# Launch_Tower_Ignition_Board_v6-4.net
KiCad netlist of a schematic drawn in EAGLE
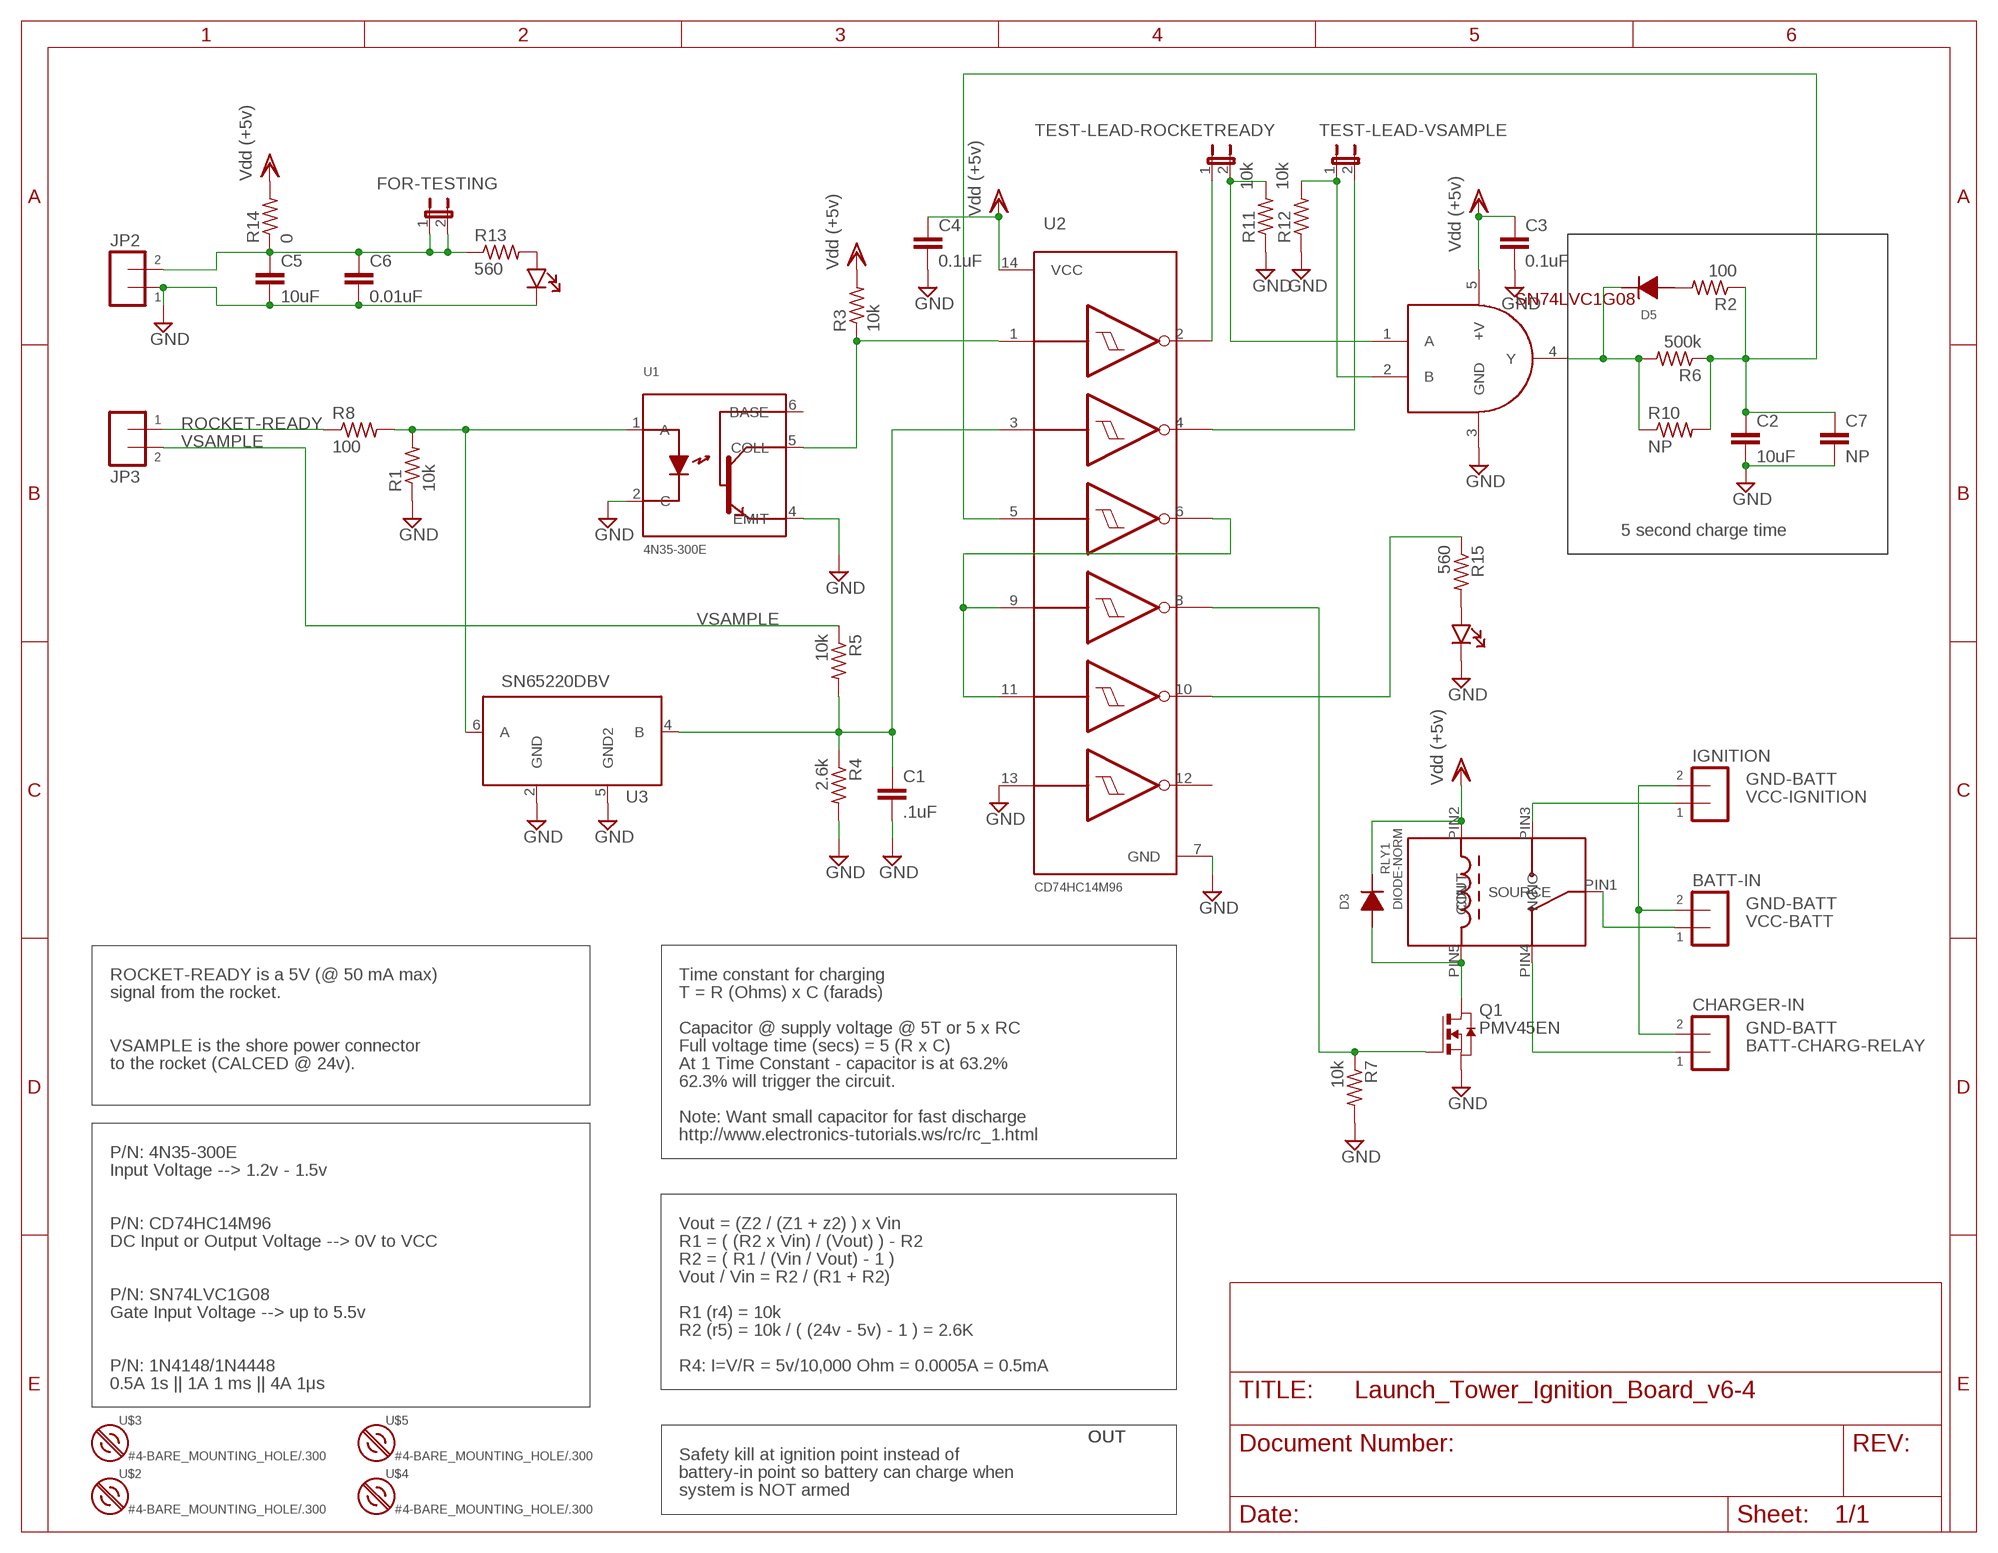
[diagram p0: schematic, sheet 1]

(export (version "E")
  (design (tool "Eeschema 10.0.6"))
  (components
    (comp (ref "BATT-IN")
      (value "SCREW-TERMINAL-5MM")
      (footprint "eagle-import:SCREW-TERM-5MM")
      (libsource (lib "eagle-import") (part "SCREW-TERMINAL-5MM"))
    )
    (comp (ref "C1")
      (value ".1uF")
      (footprint "eagle-import:0805-B")
      (libsource (lib "eagle-import") (part "C-EU0805-B"))
    )
    (comp (ref "C2")
      (value "10uF")
      (footprint "eagle-import:0805-B")
      (libsource (lib "eagle-import") (part "C-EU0805-B"))
    )
    (comp (ref "C3")
      (value "0.1uF")
      (footprint "eagle-import:0805-B")
      (libsource (lib "eagle-import") (part "C-EU0805-B"))
    )
    (comp (ref "C4")
      (value "0.1uF")
      (footprint "eagle-import:0805-B")
      (libsource (lib "eagle-import") (part "C-EU0805-B"))
    )
    (comp (ref "C5")
      (value "10uF")
      (footprint "eagle-import:0805-B")
      (libsource (lib "eagle-import") (part "C-EU0805-B"))
    )
    (comp (ref "C6")
      (value "0.01uF")
      (footprint "eagle-import:0805-B")
      (libsource (lib "eagle-import") (part "C-EU0805-B"))
    )
    (comp (ref "C7")
      (value "NP")
      (footprint "eagle-import:CAP-PTH-SMALL")
      (libsource (lib "eagle-import") (part "CAPPTH"))
    )
    (comp (ref "CHARGER-IN")
      (value "SCREW-TERMINAL-5MM")
      (footprint "eagle-import:SCREW-TERM-5MM")
      (libsource (lib "eagle-import") (part "SCREW-TERMINAL-5MM"))
    )
    (comp (ref "D3")
      (value "DIODE-NORM")
      (footprint "eagle-import:DIODE")
      (libsource (lib "eagle-import") (part "DIODE-NORM"))
    )
    (comp (ref "D5")
      (value "DIODE-NORM")
      (footprint "eagle-import:DIODE")
      (libsource (lib "eagle-import") (part "DIODE-NORM"))
    )
    (comp (ref "FOR-TESTING")
      (value "JUMPER-2PTH")
      (footprint "eagle-import:1X02")
      (libsource (lib "eagle-import") (part "JUMPER-2PTH"))
    )
    (comp (ref "IGNITION")
      (value "SCREW-TERMINAL-5MM")
      (footprint "eagle-import:SCREW-TERM-5MM")
      (libsource (lib "eagle-import") (part "SCREW-TERMINAL-5MM"))
    )
    (comp (ref "JP2")
      (value "SCREW-TERMINAL-5MM")
      (footprint "eagle-import:SCREW-TERM-5MM")
      (libsource (lib "eagle-import") (part "SCREW-TERMINAL-5MM"))
    )
    (comp (ref "JP3")
      (value "SCREW-TERMINAL-5MM")
      (footprint "eagle-import:SCREW-TERM-5MM")
      (libsource (lib "eagle-import") (part "SCREW-TERMINAL-5MM"))
    )
    (comp (ref "LED-POWER-INDICATOR")
      (value "LED-550-XX04")
      (footprint "eagle-import:LED-550")
      (libsource (lib "eagle-import") (part "LED-550-XX04"))
    )
    (comp (ref "LED-POWER-INDICATOR1")
      (value "LED-550-XX04")
      (footprint "eagle-import:LED-550")
      (libsource (lib "eagle-import") (part "LED-550-XX04"))
    )
    (comp (ref "Q1")
      (value "PMV45EN")
      (footprint "eagle-import:SOT23")
      (libsource (lib "eagle-import") (part "PMV45EN"))
    )
    (comp (ref "R1")
      (value "10k")
      (footprint "eagle-import:0805-B")
      (libsource (lib "eagle-import") (part "R-US_0805-B"))
    )
    (comp (ref "R2")
      (value "100")
      (footprint "eagle-import:0805-B")
      (libsource (lib "eagle-import") (part "R-US_0805-B"))
    )
    (comp (ref "R3")
      (value "10k")
      (footprint "eagle-import:0805-B")
      (libsource (lib "eagle-import") (part "R-US_0805-B"))
    )
    (comp (ref "R4")
      (value "2.6k")
      (footprint "eagle-import:0805-B")
      (libsource (lib "eagle-import") (part "R-US_0805-B"))
    )
    (comp (ref "R5")
      (value "10k")
      (footprint "eagle-import:0805-B")
      (libsource (lib "eagle-import") (part "R-US_0805-B"))
    )
    (comp (ref "R6")
      (value "500k")
      (footprint "eagle-import:0805-B")
      (libsource (lib "eagle-import") (part "R-US_0805-B"))
    )
    (comp (ref "R7")
      (value "10k")
      (footprint "eagle-import:0805-B")
      (libsource (lib "eagle-import") (part "R-US_0805-B"))
    )
    (comp (ref "R8")
      (value "100")
      (footprint "eagle-import:0805-B")
      (libsource (lib "eagle-import") (part "R-US_0805-B"))
    )
    (comp (ref "R10")
      (value "NP")
      (footprint "eagle-import:0207_10")
      (libsource (lib "eagle-import") (part "R-US_0207/10"))
    )
    (comp (ref "R11")
      (value "10k")
      (footprint "eagle-import:0805-B")
      (libsource (lib "eagle-import") (part "R-US_0805-B"))
    )
    (comp (ref "R12")
      (value "10k")
      (footprint "eagle-import:0805-B")
      (libsource (lib "eagle-import") (part "R-US_0805-B"))
    )
    (comp (ref "R13")
      (value "560")
      (footprint "eagle-import:0805-B")
      (libsource (lib "eagle-import") (part "R-US_0805-B"))
    )
    (comp (ref "R14")
      (value "0")
      (footprint "eagle-import:0805-B")
      (libsource (lib "eagle-import") (part "R-US_0805-B"))
    )
    (comp (ref "R15")
      (value "560")
      (footprint "eagle-import:0805-B")
      (libsource (lib "eagle-import") (part "R-US_0805-B"))
    )
    (comp (ref "RLY1")
      (value "RELAY-2")
      (footprint "eagle-import:G5LA")
      (libsource (lib "eagle-import") (part "RELAY-2"))
    )
    (comp (ref "TEST-LEAD-ROCKETREADY")
      (value "JUMPER-2PTH")
      (footprint "eagle-import:1X02")
      (libsource (lib "eagle-import") (part "JUMPER-2PTH"))
    )
    (comp (ref "TEST-LEAD-VSAMPLE")
      (value "JUMPER-2PTH")
      (footprint "eagle-import:1X02")
      (libsource (lib "eagle-import") (part "JUMPER-2PTH"))
    )
    (comp (ref "U$2")
      (value "#4-BARE_MOUNTING_HOLE/.300")
      (footprint "eagle-import:#4_.300-BARE+STD_NUT_OR_STAR_WASHER")
      (libsource (lib "eagle-import") (part "#4-BARE_MOUNTING_HOLE/.300"))
    )
    (comp (ref "U$3")
      (value "#4-BARE_MOUNTING_HOLE/.300")
      (footprint "eagle-import:#4_.300-BARE+STD_NUT_OR_STAR_WASHER")
      (libsource (lib "eagle-import") (part "#4-BARE_MOUNTING_HOLE/.300"))
    )
    (comp (ref "U$4")
      (value "#4-BARE_MOUNTING_HOLE/.300")
      (footprint "eagle-import:#4_.300-BARE+STD_NUT_OR_STAR_WASHER")
      (libsource (lib "eagle-import") (part "#4-BARE_MOUNTING_HOLE/.300"))
    )
    (comp (ref "U$5")
      (value "#4-BARE_MOUNTING_HOLE/.300")
      (footprint "eagle-import:#4_.300-BARE+STD_NUT_OR_STAR_WASHER")
      (libsource (lib "eagle-import") (part "#4-BARE_MOUNTING_HOLE/.300"))
    )
    (comp (ref "U1")
      (value "OPTOISOLATOR")
      (footprint "eagle-import:4N35-300E")
      (libsource (lib "eagle-import") (part "OPTOISOLATOR"))
    )
    (comp (ref "U2")
      (value "INVERT GATES")
      (footprint "eagle-import:INVERTSOIC14")
      (libsource (lib "eagle-import") (part "HEX_INV_SHMITT_TRIG"))
    )
    (comp (ref "U3")
      (value "SN65220DBV")
      (footprint "eagle-import:SOT23-6L")
      (libsource (lib "eagle-import") (part "SN65220DBV"))
    )
    (comp (ref "U4")
      (value "AND GATE")
      (footprint "eagle-import:SOT23-5")
      (libsource (lib "eagle-import") (part "SN74LVC1G08"))
    )
  )
  (nets
    (net (code "1") (name "/BATT-CHARG-RELAY") (class "Default")
      (node (ref "CHARGER-IN") (pin "1") (pinfunction "1_1") (pintype "passive"))
      (node (ref "RLY1") (pin "PIN4") (pinfunction "NC_PIN4") (pintype "bidirectional"))
    )
    (net (code "2") (name "/GND-BATT") (class "Default")
      (node (ref "BATT-IN") (pin "2") (pinfunction "2_2") (pintype "passive"))
      (node (ref "CHARGER-IN") (pin "2") (pinfunction "2_2") (pintype "passive"))
      (node (ref "IGNITION") (pin "2") (pinfunction "2_2") (pintype "passive"))
    )
    (net (code "3") (name "/ROCKET-READY") (class "Default")
      (node (ref "R1") (pin "2") (pinfunction "2_2") (pintype "passive"))
      (node (ref "R8") (pin "2") (pinfunction "2_2") (pintype "passive"))
      (node (ref "U1") (pin "1") (pinfunction "A_1") (pintype "passive"))
      (node (ref "U3") (pin "6") (pinfunction "A_6") (pintype "passive"))
    )
    (net (code "4") (name "/VCC-BATT") (class "Default")
      (node (ref "BATT-IN") (pin "1") (pinfunction "1_1") (pintype "passive"))
      (node (ref "RLY1") (pin "PIN1") (pinfunction "SOURCE_PIN1") (pintype "bidirectional"))
    )
    (net (code "5") (name "/VCC-IGNITION") (class "Default")
      (node (ref "IGNITION") (pin "1") (pinfunction "1_1") (pintype "passive"))
      (node (ref "RLY1") (pin "PIN3") (pinfunction "NO_PIN3") (pintype "bidirectional"))
    )
    (net (code "6") (name "/VSAMPLE") (class "Default")
      (node (ref "JP3") (pin "2") (pinfunction "2_2") (pintype "passive"))
      (node (ref "R5") (pin "1") (pinfunction "1_1") (pintype "passive"))
    )
    (net (code "7") (name "GND") (class "Default")
      (node (ref "C1") (pin "2") (pinfunction "2_2") (pintype "passive"))
      (node (ref "C2") (pin "2") (pinfunction "2_2") (pintype "passive"))
      (node (ref "C3") (pin "2") (pinfunction "2_2") (pintype "passive"))
      (node (ref "C4") (pin "2") (pinfunction "2_2") (pintype "passive"))
      (node (ref "C5") (pin "2") (pinfunction "2_2") (pintype "passive"))
      (node (ref "C6") (pin "2") (pinfunction "2_2") (pintype "passive"))
      (node (ref "C7") (pin "2") (pinfunction "2_2") (pintype "passive"))
      (node (ref "JP2") (pin "1") (pinfunction "1_1") (pintype "passive"))
      (node (ref "LED-POWER-INDICATOR") (pin "CATHODE") (pinfunction "CATHODE_CATHODE") (pintype "bidirectional"))
      (node (ref "LED-POWER-INDICATOR1") (pin "CATHODE") (pinfunction "CATHODE_CATHODE") (pintype "bidirectional"))
      (node (ref "Q1") (pin "2") (pinfunction "S_2") (pintype "passive"))
      (node (ref "R1") (pin "1") (pinfunction "1_1") (pintype "passive"))
      (node (ref "R11") (pin "1") (pinfunction "1_1") (pintype "passive"))
      (node (ref "R12") (pin "1") (pinfunction "1_1") (pintype "passive"))
      (node (ref "R4") (pin "2") (pinfunction "2_2") (pintype "passive"))
      (node (ref "R7") (pin "2") (pinfunction "2_2") (pintype "passive"))
      (node (ref "U1") (pin "2") (pinfunction "C_2") (pintype "passive"))
      (node (ref "U1") (pin "4") (pinfunction "EMIT_4") (pintype "passive"))
      (node (ref "U2") (pin "13") (pinfunction "6A_13") (pintype "input"))
      (node (ref "U2") (pin "7") (pinfunction "GND_7") (pintype "bidirectional"))
      (node (ref "U3") (pin "2") (pinfunction "GND_2") (pintype "power_in"))
      (node (ref "U3") (pin "5") (pinfunction "GND2_5") (pintype "power_in"))
      (node (ref "U4") (pin "3") (pinfunction "GND_3") (pintype "bidirectional"))
    )
    (net (code "8") (name "Net-(C5-Pad1)") (class "Default")
      (node (ref "C5") (pin "1") (pinfunction "1_1") (pintype "passive"))
      (node (ref "C6") (pin "1") (pinfunction "1_1") (pintype "passive"))
      (node (ref "FOR-TESTING") (pin "1") (pinfunction "1_1") (pintype "passive"))
      (node (ref "FOR-TESTING") (pin "2") (pinfunction "2_2") (pintype "passive"))
      (node (ref "JP2") (pin "2") (pinfunction "2_2") (pintype "passive"))
      (node (ref "R13") (pin "1") (pinfunction "1_1") (pintype "passive"))
      (node (ref "R14") (pin "1") (pinfunction "1_1") (pintype "passive"))
    )
    (net (code "9") (name "Net-(D5-PadA)") (class "Default")
      (node (ref "D5") (pin "A") (pinfunction "A_A") (pintype "passive"))
      (node (ref "R2") (pin "2") (pinfunction "2_2") (pintype "passive"))
    )
    (net (code "10") (name "Net-(JP3-Pad1)") (class "Default")
      (node (ref "JP3") (pin "1") (pinfunction "1_1") (pintype "passive"))
      (node (ref "R8") (pin "1") (pinfunction "1_1") (pintype "passive"))
    )
    (net (code "11") (name "Net-(LED-POWER-INDICATOR-PadANODE)") (class "Default")
      (node (ref "LED-POWER-INDICATOR") (pin "ANODE") (pinfunction "ANODE_ANODE") (pintype "bidirectional"))
      (node (ref "R13") (pin "2") (pinfunction "2_2") (pintype "passive"))
    )
    (net (code "12") (name "Net-(LED-POWER-INDICATOR1-PadANODE)") (class "Default")
      (node (ref "LED-POWER-INDICATOR1") (pin "ANODE") (pinfunction "ANODE_ANODE") (pintype "bidirectional"))
      (node (ref "R15") (pin "2") (pinfunction "2_2") (pintype "passive"))
    )
    (net (code "13") (name "Net-(Q1-D)") (class "Default")
      (node (ref "D3") (pin "A") (pinfunction "A_A") (pintype "passive"))
      (node (ref "Q1") (pin "3") (pinfunction "D_3") (pintype "passive"))
      (node (ref "RLY1") (pin "PIN5") (pinfunction "CIN_PIN5") (pintype "bidirectional"))
    )
    (net (code "14") (name "Net-(Q1-G)") (class "Default")
      (node (ref "Q1") (pin "1") (pinfunction "G_1") (pintype "passive"))
      (node (ref "R7") (pin "1") (pinfunction "1_1") (pintype "passive"))
      (node (ref "U2") (pin "8") (pinfunction "4Y_8") (pintype "output"))
    )
    (net (code "15") (name "Net-(U1-COLL)") (class "Default")
      (node (ref "R3") (pin "1") (pinfunction "1_1") (pintype "passive"))
      (node (ref "U1") (pin "5") (pinfunction "COLL_5") (pintype "passive"))
      (node (ref "U2") (pin "1") (pinfunction "1A_1") (pintype "input"))
    )
    (net (code "16") (name "Net-(U2-1Y)") (class "Default")
      (node (ref "TEST-LEAD-ROCKETREADY") (pin "1") (pinfunction "1_1") (pintype "passive"))
      (node (ref "U2") (pin "2") (pinfunction "1Y_2") (pintype "output"))
    )
    (net (code "17") (name "Net-(U2-2A)") (class "Default")
      (node (ref "C1") (pin "1") (pinfunction "1_1") (pintype "passive"))
      (node (ref "R4") (pin "1") (pinfunction "1_1") (pintype "passive"))
      (node (ref "R5") (pin "2") (pinfunction "2_2") (pintype "passive"))
      (node (ref "U2") (pin "3") (pinfunction "2A_3") (pintype "input"))
      (node (ref "U3") (pin "4") (pinfunction "B_4") (pintype "passive"))
    )
    (net (code "18") (name "Net-(U2-2Y)") (class "Default")
      (node (ref "TEST-LEAD-VSAMPLE") (pin "2") (pinfunction "2_2") (pintype "passive"))
      (node (ref "U2") (pin "4") (pinfunction "2Y_4") (pintype "output"))
    )
    (net (code "19") (name "Net-(U2-3A)") (class "Default")
      (node (ref "C2") (pin "1") (pinfunction "1_1") (pintype "passive"))
      (node (ref "C7") (pin "1") (pinfunction "1_1") (pintype "passive"))
      (node (ref "R10") (pin "2") (pinfunction "2_2") (pintype "passive"))
      (node (ref "R2") (pin "1") (pinfunction "1_1") (pintype "passive"))
      (node (ref "R6") (pin "1") (pinfunction "1_1") (pintype "passive"))
      (node (ref "U2") (pin "5") (pinfunction "3A_5") (pintype "input"))
    )
    (net (code "20") (name "Net-(U2-3Y)") (class "Default")
      (node (ref "U2") (pin "11") (pinfunction "5A_11") (pintype "input"))
      (node (ref "U2") (pin "6") (pinfunction "3Y_6") (pintype "output"))
      (node (ref "U2") (pin "9") (pinfunction "4A_9") (pintype "input"))
    )
    (net (code "21") (name "Net-(U2-5Y)") (class "Default")
      (node (ref "R15") (pin "1") (pinfunction "1_1") (pintype "passive"))
      (node (ref "U2") (pin "10") (pinfunction "5Y_10") (pintype "output"))
    )
    (net (code "22") (name "Net-(U4-A)") (class "Default")
      (node (ref "R11") (pin "2") (pinfunction "2_2") (pintype "passive"))
      (node (ref "TEST-LEAD-ROCKETREADY") (pin "2") (pinfunction "2_2") (pintype "passive"))
      (node (ref "U4") (pin "1") (pinfunction "A_1") (pintype "bidirectional"))
    )
    (net (code "23") (name "Net-(U4-B)") (class "Default")
      (node (ref "R12") (pin "2") (pinfunction "2_2") (pintype "passive"))
      (node (ref "TEST-LEAD-VSAMPLE") (pin "1") (pinfunction "1_1") (pintype "passive"))
      (node (ref "U4") (pin "2") (pinfunction "B_2") (pintype "bidirectional"))
    )
    (net (code "24") (name "Net-(U4-Y)") (class "Default")
      (node (ref "D5") (pin "C") (pinfunction "C_C") (pintype "passive"))
      (node (ref "R10") (pin "1") (pinfunction "1_1") (pintype "passive"))
      (node (ref "R6") (pin "2") (pinfunction "2_2") (pintype "passive"))
      (node (ref "U4") (pin "4") (pinfunction "Y_4") (pintype "bidirectional"))
    )
    (net (code "25") (name "Vdd (+5v)") (class "Default")
      (node (ref "C3") (pin "1") (pinfunction "1_1") (pintype "passive"))
      (node (ref "C4") (pin "1") (pinfunction "1_1") (pintype "passive"))
      (node (ref "D3") (pin "C") (pinfunction "C_C") (pintype "passive"))
      (node (ref "R14") (pin "2") (pinfunction "2_2") (pintype "passive"))
      (node (ref "R3") (pin "2") (pinfunction "2_2") (pintype "passive"))
      (node (ref "RLY1") (pin "PIN2") (pinfunction "COUT_PIN2") (pintype "bidirectional"))
      (node (ref "U2") (pin "14") (pinfunction "VCC_14") (pintype "bidirectional"))
      (node (ref "U4") (pin "5") (pinfunction "+V_5") (pintype "bidirectional"))
    )
    (net (code "26") (name "unconnected-(U1-BASE-Pad6)") (class "Default")
      (node (ref "U1") (pin "6") (pinfunction "BASE_6") (pintype "passive"))
    )
    (net (code "27") (name "unconnected-(U2-6Y-Pad12)") (class "Default")
      (node (ref "U2") (pin "12") (pinfunction "6Y_12") (pintype "output"))
    )
  )
)
